# Sheet1.net
KiCad netlist of a schematic drawn in Altium Designer
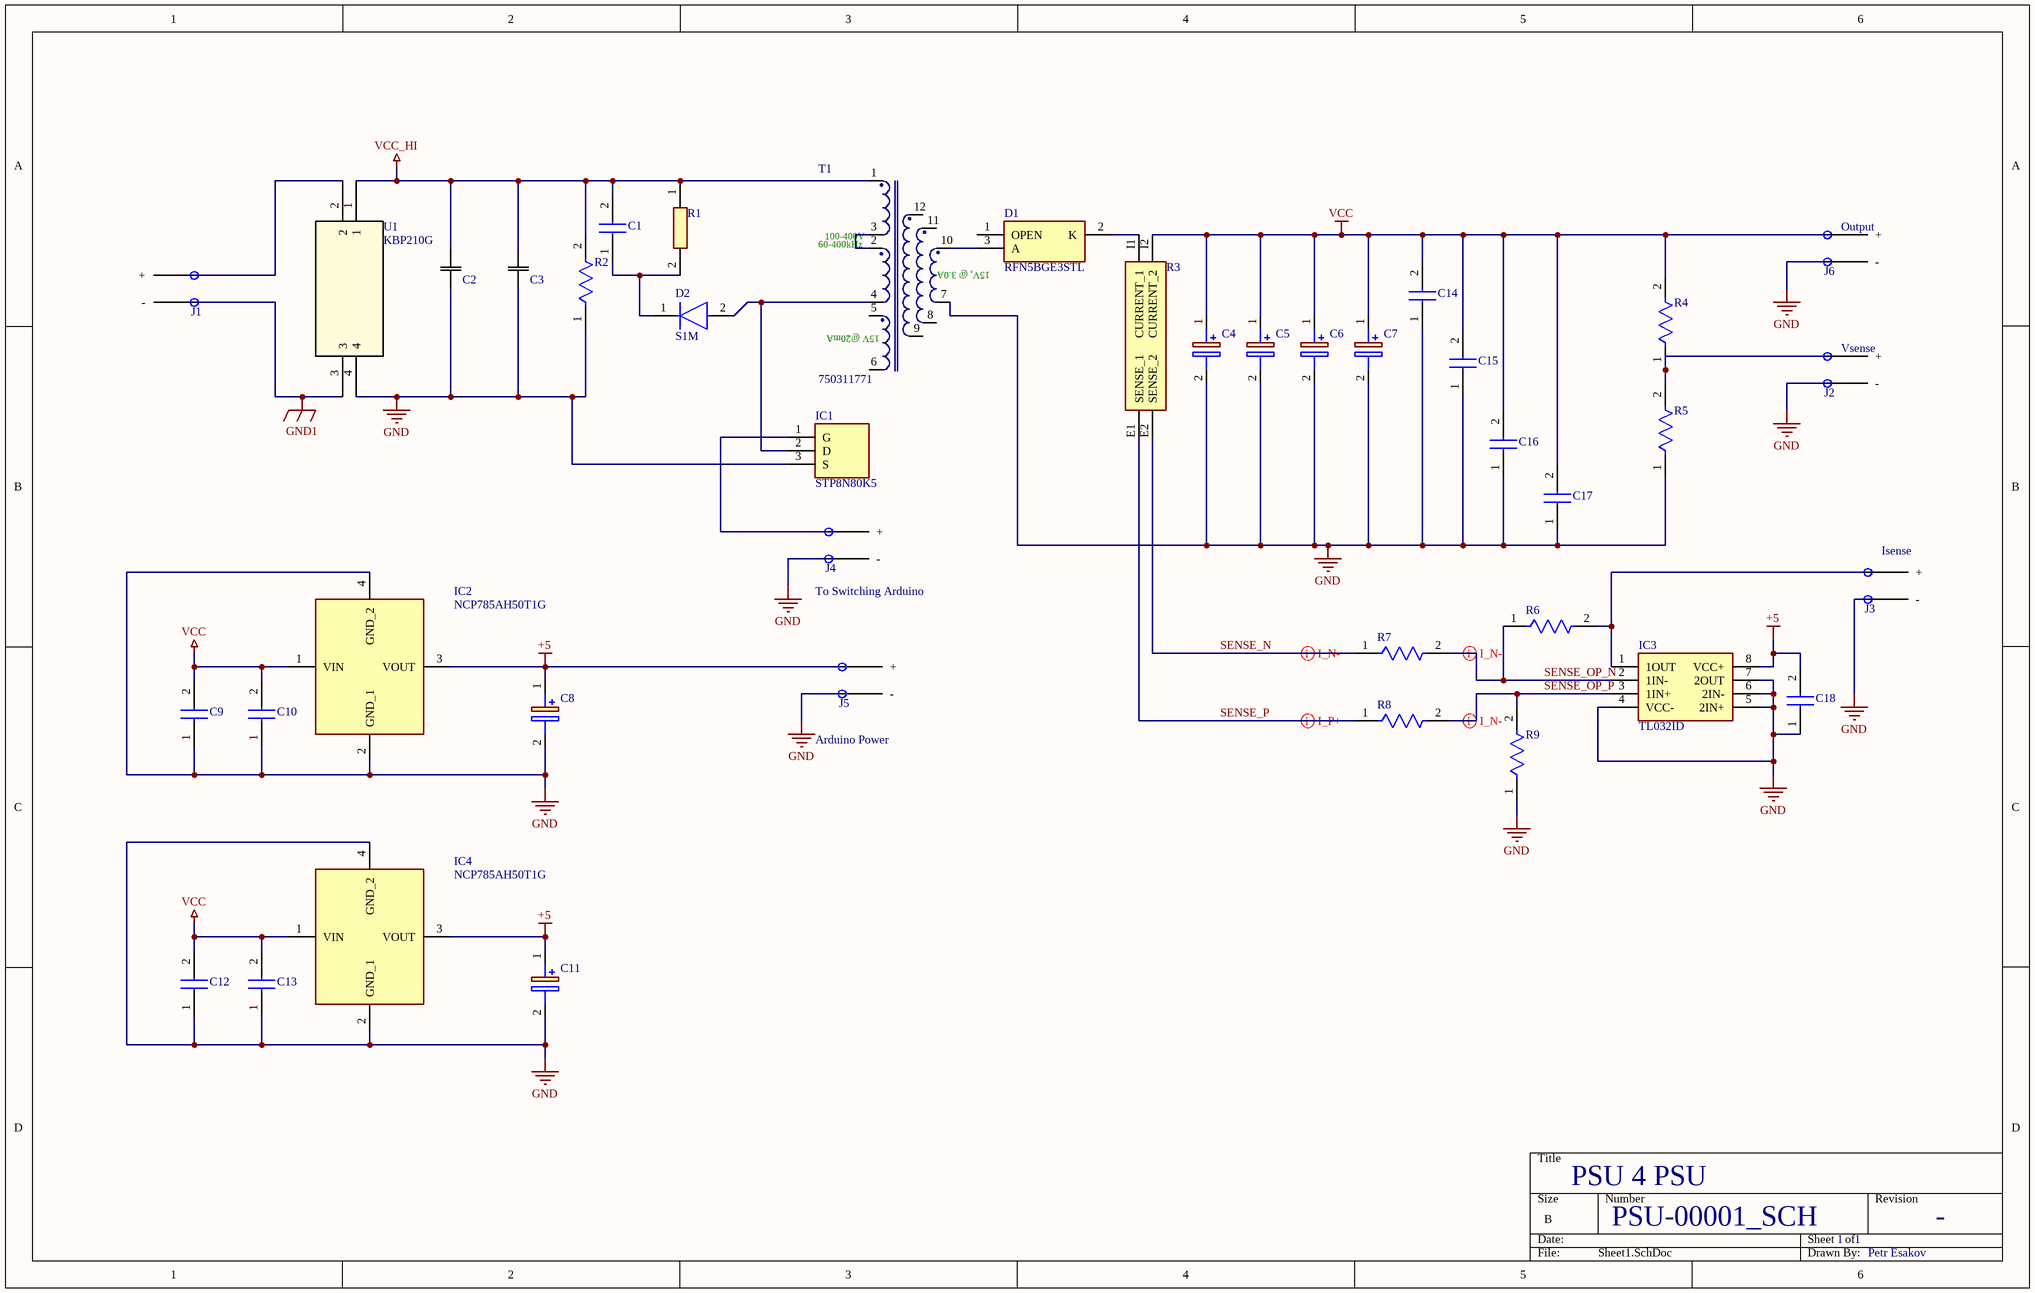
[diagram p0: Sheet1.SchDoc]

(export (version "E")
  (design (tool "Eeschema 10.0.6"))
  (components
    (comp (ref "C1")
      (value "C2220C105K2RACTU")
      (footprint "SamacSys:C2220")
      (description "Capacitor")
      (libsource (lib "*") (part "C2220C105K2RACTU"))
    )
    (comp (ref "C2")
      (value "500HXW100MEFR18X45")
      (footprint "CAP_HXW_18X45_RUB")
      (description "No Description Available")
      (libsource (lib "500HXW100MEFR18X45") (part "500HXW100MEFR18X45"))
    )
    (comp (ref "C3")
      (value "500HXW100MEFR18X45")
      (footprint "CAP_HXW_18X45_RUB")
      (description "No Description Available")
      (libsource (lib "500HXW100MEFR18X45") (part "500HXW100MEFR18X45"))
    )
    (comp (ref "C4")
      (value "EGXF630ELL511MK25S")
      (footprint "SamacSys:CAPPRD500W60D1275H2650")
      (description "Capacitor Polarised")
      (fields (field (name "MOUSER PART NUMBER") "661-EGXF630ELL511MK2"))
      (libsource (lib "*") (part "EGXF630ELL511MK25S"))
    )
    (comp (ref "C5")
      (value "EGXF630ELL511MK25S")
      (footprint "SamacSys:CAPPRD500W60D1275H2650")
      (description "Capacitor Polarised")
      (fields (field (name "MOUSER PART NUMBER") "661-EGXF630ELL511MK2"))
      (libsource (lib "*") (part "EGXF630ELL511MK25S"))
    )
    (comp (ref "C6")
      (value "EGXF630ELL511MK25S")
      (footprint "SamacSys:CAPPRD500W60D1275H2650")
      (description "Capacitor Polarised")
      (fields (field (name "MOUSER PART NUMBER") "661-EGXF630ELL511MK2"))
      (libsource (lib "*") (part "EGXF630ELL511MK25S"))
    )
    (comp (ref "C7")
      (value "EGXF630ELL511MK25S")
      (footprint "SamacSys:CAPPRD500W60D1275H2650")
      (description "Capacitor Polarised")
      (fields (field (name "MOUSER PART NUMBER") "661-EGXF630ELL511MK2"))
      (libsource (lib "*") (part "EGXF630ELL511MK25S"))
    )
    (comp (ref "C8")
      (value "MAL202139229E3")
      (footprint "SamacSys:CAPPA4610W80L1850D690")
      (description "Capacitor Polarised")
      (fields (field (name "MOUSER PART NUMBER") "594-2222-021-39229"))
      (libsource (lib "*") (part "MAL202139229E3"))
    )
    (comp (ref "C9")
      (value "ECW-FD2J105J")
      (footprint "SamacSys:ECWFD2J105J")
      (description "Capacitor")
      (fields (field (name "MOUSER PART NUMBER") "667-ECW-FD2J105J"))
      (libsource (lib "*") (part "ECW-FD2J105J"))
    )
    (comp (ref "C10")
      (value "ECW-FD2J105J")
      (footprint "SamacSys:ECWFD2J105J")
      (description "Capacitor")
      (fields (field (name "MOUSER PART NUMBER") "667-ECW-FD2J105J"))
      (libsource (lib "*") (part "ECW-FD2J105J"))
    )
    (comp (ref "C11")
      (value "MAL202139229E3")
      (footprint "SamacSys:CAPPA4610W80L1850D690")
      (description "Capacitor Polarised")
      (fields (field (name "MOUSER PART NUMBER") "594-2222-021-39229"))
      (libsource (lib "*") (part "MAL202139229E3"))
    )
    (comp (ref "C12")
      (value "ECW-FD2J105J")
      (footprint "SamacSys:ECWFD2J105J")
      (description "Capacitor")
      (fields (field (name "MOUSER PART NUMBER") "667-ECW-FD2J105J"))
      (libsource (lib "*") (part "ECW-FD2J105J"))
    )
    (comp (ref "C13")
      (value "ECW-FD2J105J")
      (footprint "SamacSys:ECWFD2J105J")
      (description "Capacitor")
      (fields (field (name "MOUSER PART NUMBER") "667-ECW-FD2J105J"))
      (libsource (lib "*") (part "ECW-FD2J105J"))
    )
    (comp (ref "C14")
      (value "K104K15X7RF5TH5")
      (footprint "SamacSys:K104K15X7RF5TH5")
      (description "Capacitor")
      (fields (field (name "MOUSER PART NUMBER") "594-K104K15X7RF5TH5"))
      (libsource (lib "*") (part "K104K15X7RF5TH5"))
    )
    (comp (ref "C15")
      (value "K104K15X7RF5TH5")
      (footprint "SamacSys:K104K15X7RF5TH5")
      (description "Capacitor")
      (fields (field (name "MOUSER PART NUMBER") "594-K104K15X7RF5TH5"))
      (libsource (lib "*") (part "K104K15X7RF5TH5"))
    )
    (comp (ref "C16")
      (value "K104K15X7RF5TH5")
      (footprint "SamacSys:K104K15X7RF5TH5")
      (description "Capacitor")
      (fields (field (name "MOUSER PART NUMBER") "594-K104K15X7RF5TH5"))
      (libsource (lib "*") (part "K104K15X7RF5TH5"))
    )
    (comp (ref "C17")
      (value "K104K15X7RF5TH5")
      (footprint "SamacSys:K104K15X7RF5TH5")
      (description "Capacitor")
      (fields (field (name "MOUSER PART NUMBER") "594-K104K15X7RF5TH5"))
      (libsource (lib "*") (part "K104K15X7RF5TH5"))
    )
    (comp (ref "C18")
      (value "K104K15X7RF5TH5")
      (footprint "SamacSys:K104K15X7RF5TH5")
      (description "Capacitor")
      (fields (field (name "MOUSER PART NUMBER") "594-K104K15X7RF5TH5"))
      (libsource (lib "*") (part "K104K15X7RF5TH5"))
    )
    (comp (ref "D1")
      (value "RFN5BGE3STL")
      (footprint "SamacSys:RD3P175SNFRATL")
      (description "Diode")
      (fields (field (name "MOUSER PART NUMBER") "755-RFN5BGE3STL"))
      (libsource (lib "*") (part "RFN5BGE3STL"))
    )
    (comp (ref "D2")
      (value "S1M")
      (footprint "FP-403AE-MFG")
      (description "DIODE GEN PURP 1KV 1A SMA")
      (fields (field (name "VOLTAGE") "1kV"))
      (libsource (lib "Altium Content Vault") (part "d7152d700b627762746794eb795d46e"))
    )
    (comp (ref "IC1")
      (value "STP8N80K5")
      (footprint "SamacSys:TO255P460X1020X2008-3P")
      (description "Integrated Circuit")
      (fields (field (name "MOUSER PART NUMBER") "511-STP8N80K5"))
      (libsource (lib "*") (part "STP8N80K5"))
    )
    (comp (ref "IC2")
      (value "NCP785AH50T1G")
      (footprint "SamacSys:NCP785AH50T1G")
      (description "Integrated Circuit")
      (fields (field (name "MOUSER PART NUMBER") "863-NCP785AH50T1G"))
      (libsource (lib "*") (part "NCP785AH50T1G"))
    )
    (comp (ref "IC3")
      (value "TL032ID")
      (footprint "SamacSys:SOIC127P600X175-8N")
      (description "Integrated Circuit")
      (fields (field (name "MOUSER PART NUMBER") "595-TL032ID"))
      (libsource (lib "*") (part "TL032ID"))
    )
    (comp (ref "IC4")
      (value "NCP785AH50T1G")
      (footprint "SamacSys:NCP785AH50T1G")
      (description "Integrated Circuit")
      (fields (field (name "MOUSER PART NUMBER") "863-NCP785AH50T1G"))
      (libsource (lib "*") (part "NCP785AH50T1G"))
    )
    (comp (ref "J1")
      (value "Component_1")
      (footprint "PCBComponent_1")
      (libsource (lib "Integrated_Library1") (part "Component_1"))
    )
    (comp (ref "J2")
      (value "Component_1")
      (footprint "PCBComponent_1")
      (libsource (lib "Integrated_Library1") (part "Component_1"))
    )
    (comp (ref "J3")
      (value "Component_1")
      (footprint "PCBComponent_1")
      (libsource (lib "Integrated_Library1") (part "Component_1"))
    )
    (comp (ref "J4")
      (value "Component_1")
      (footprint "PCBComponent_1")
      (libsource (lib "Integrated_Library1") (part "Component_1"))
    )
    (comp (ref "J5")
      (value "Component_1")
      (footprint "PCBComponent_1")
      (libsource (lib "Integrated_Library1") (part "Component_1"))
    )
    (comp (ref "J6")
      (value "Component_1")
      (footprint "PCBComponent_1")
      (libsource (lib "Integrated_Library1") (part "Component_1"))
    )
    (comp (ref "R1")
      (value "MRS25000C7500FRP00")
      (footprint "SamacSys:RESAD1650W60L650D250")
      (description "Resistor")
      (libsource (lib "*") (part "MRS25000C7500FRP00"))
    )
    (comp (ref "R2")
      (value "CRCW251210K0JNEG")
      (footprint "FP-CRCW2512-e3-IPC_A")
      (description "RES Thick Film, 10kΩ, 5%, 1W, 200ppm/°C, 2512")
      (fields (field (name "TOLERANCE") "5%"))
      (libsource (lib "Altium Content Vault") (part "1029c3af85768c4190bb7ad29bc67b5"))
    )
    (comp (ref "R3")
      (value "Y14870R10000B9R")
      (footprint "SamacSys:Y14870R10000B9R")
      (description "Resistor")
      (fields (field (name "MOUSER PART NUMBER") "71-CSM25120R1000BST"))
      (libsource (lib "*") (part "Y14870R10000B9R"))
    )
    (comp (ref "R4")
      (value "CR0805-FX-1003ELF")
      (footprint "FP-CR0805-IPC_B")
      (description "Thick Film Chip Resistors 0805 100kΩ 0.125W 1% 100ppm/°C")
      (fields (field (name "TOLERANCE") "1%"))
      (libsource (lib "Altium Content Vault") (part "1029c3af85768c4190bb7ad29bc67b5"))
    )
    (comp (ref "R5")
      (value "CRCW080520K0FKTA")
      (footprint "FP-CRCW0805-e3-IPC_B")
      (description "RES Thick Film, 20kΩ, 1%, 0.125W, 100ppm/°C, 0805")
      (fields (field (name "TOLERANCE") "1%"))
      (libsource (lib "Altium Content Vault") (part "1029c3af85768c4190bb7ad29bc67b5"))
    )
    (comp (ref "R6")
      (value "CRCW0805330KFKEA")
      (footprint "FP-CRCW0805-e3-MFG")
      (description "RES Thick Film, 330kΩ, 1%, 0.125W, 100ppm/°C, 0805")
      (fields (field (name "TOLERANCE") "1%"))
      (libsource (lib "Altium Content Vault") (part "1029c3af85768c4190bb7ad29bc67b5"))
    )
    (comp (ref "R7")
      (value "CRCW080520K0FKEB")
      (footprint "FP-CRCW0805-e3-IPC_B")
      (description "RES Thick Film, 20kΩ, 1%, 0.125W, 100ppm/°C, 0805")
      (fields (field (name "TOLERANCE") "1%"))
      (libsource (lib "Altium Content Vault") (part "1029c3af85768c4190bb7ad29bc67b5"))
    )
    (comp (ref "R8")
      (value "CRCW080520K0FKEB")
      (footprint "FP-CRCW0805-e3-IPC_B")
      (description "RES Thick Film, 20kΩ, 1%, 0.125W, 100ppm/°C, 0805")
      (fields (field (name "TOLERANCE") "1%"))
      (libsource (lib "Altium Content Vault") (part "1029c3af85768c4190bb7ad29bc67b5"))
    )
    (comp (ref "R9")
      (value "CRCW0805330KFKEA")
      (footprint "FP-CRCW0805-e3-MFG")
      (description "RES Thick Film, 330kΩ, 1%, 0.125W, 100ppm/°C, 0805")
      (fields (field (name "TOLERANCE") "1%"))
      (libsource (lib "Altium Content Vault") (part "1029c3af85768c4190bb7ad29bc67b5"))
    )
    (comp (ref "T1")
      (value "750311771")
      (footprint "EFD25")
      (description "Flyback Transformer suitable or LT3573/ LT3574/ LT3575/ LT3748 WE-FB, Ui=100-400V")
      (fields (field (name "MANUFACTURER") "Wuerth Elektronik"))
      (libsource (lib "Altium Content Vault") (part "WE-750311771"))
    )
    (comp (ref "U1")
      (value "KBP210G")
      (footprint "TO_P2005G_DIO")
      (description "No Description Available")
      (libsource (lib "KBP210G") (part "KBP210G"))
    )
  )
  (nets
    (net (code "1") (name "+5") (class "Default")
      (node (ref "C11") (pin "1") (pinfunction "+_1") (pintype "passive"))
      (node (ref "C18") (pin "2") (pinfunction "2_2") (pintype "passive"))
      (node (ref "C8") (pin "1") (pinfunction "+_1") (pintype "passive"))
      (node (ref "IC2") (pin "3") (pinfunction "VOUT_3") (pintype "passive"))
      (node (ref "IC3") (pin "8") (pinfunction "VCC+_8") (pintype "passive"))
      (node (ref "IC4") (pin "3") (pinfunction "VOUT_3") (pintype "passive"))
      (node (ref "J5") (pin "0") (pinfunction "+_0") (pintype "passive"))
    )
    (net (code "2") (name "/SENSE_N") (class "Default")
      (node (ref "R3") (pin "E2") (pinfunction "SENSE_2_E2") (pintype "passive"))
      (node (ref "R7") (pin "1") (pinfunction "1_1") (pintype "passive"))
    )
    (net (code "3") (name "/SENSE_OP_N") (class "Default")
      (node (ref "IC3") (pin "2") (pinfunction "1IN-_2") (pintype "passive"))
      (node (ref "R6") (pin "1") (pinfunction "1_1") (pintype "passive"))
      (node (ref "R7") (pin "2") (pinfunction "2_2") (pintype "passive"))
    )
    (net (code "4") (name "/SENSE_OP_P") (class "Default")
      (node (ref "IC3") (pin "3") (pinfunction "1IN+_3") (pintype "passive"))
      (node (ref "R8") (pin "2") (pinfunction "2_2") (pintype "passive"))
      (node (ref "R9") (pin "2") (pinfunction "2_2") (pintype "passive"))
    )
    (net (code "5") (name "/SENSE_P") (class "Default")
      (node (ref "R3") (pin "E1") (pinfunction "SENSE_1_E1") (pintype "passive"))
      (node (ref "R8") (pin "1") (pinfunction "1_1") (pintype "passive"))
    )
    (net (code "6") (name "GND") (class "Default")
      (node (ref "C10") (pin "1") (pinfunction "1_1") (pintype "passive"))
      (node (ref "C11") (pin "2") (pinfunction "-_2") (pintype "passive"))
      (node (ref "C12") (pin "1") (pinfunction "1_1") (pintype "passive"))
      (node (ref "C13") (pin "1") (pinfunction "1_1") (pintype "passive"))
      (node (ref "C14") (pin "1") (pinfunction "1_1") (pintype "passive"))
      (node (ref "C15") (pin "1") (pinfunction "1_1") (pintype "passive"))
      (node (ref "C16") (pin "1") (pinfunction "1_1") (pintype "passive"))
      (node (ref "C17") (pin "1") (pinfunction "1_1") (pintype "passive"))
      (node (ref "C18") (pin "1") (pinfunction "1_1") (pintype "passive"))
      (node (ref "C2") (pin "1") (pinfunction "1_1") (pintype "passive"))
      (node (ref "C3") (pin "1") (pinfunction "1_1") (pintype "passive"))
      (node (ref "C4") (pin "2") (pinfunction "-_2") (pintype "passive"))
      (node (ref "C5") (pin "2") (pinfunction "-_2") (pintype "passive"))
      (node (ref "C6") (pin "2") (pinfunction "-_2") (pintype "passive"))
      (node (ref "C7") (pin "2") (pinfunction "-_2") (pintype "passive"))
      (node (ref "C8") (pin "2") (pinfunction "-_2") (pintype "passive"))
      (node (ref "C9") (pin "1") (pinfunction "1_1") (pintype "passive"))
      (node (ref "IC1") (pin "3") (pinfunction "S_3") (pintype "passive"))
      (node (ref "IC2") (pin "2") (pinfunction "GND_1_2") (pintype "passive"))
      (node (ref "IC2") (pin "4") (pinfunction "GND_2_4") (pintype "passive"))
      (node (ref "IC3") (pin "4") (pinfunction "VCC-_4") (pintype "passive"))
      (node (ref "IC3") (pin "5") (pinfunction "2IN+_5") (pintype "passive"))
      (node (ref "IC3") (pin "6") (pinfunction "2IN-_6") (pintype "passive"))
      (node (ref "IC3") (pin "7") (pinfunction "2OUT_7") (pintype "passive"))
      (node (ref "IC4") (pin "2") (pinfunction "GND_1_2") (pintype "passive"))
      (node (ref "IC4") (pin "4") (pinfunction "GND_2_4") (pintype "passive"))
      (node (ref "J2") (pin "1") (pinfunction "-_1") (pintype "passive"))
      (node (ref "J3") (pin "1") (pinfunction "-_1") (pintype "passive"))
      (node (ref "J4") (pin "1") (pinfunction "-_1") (pintype "passive"))
      (node (ref "J5") (pin "1") (pinfunction "-_1") (pintype "passive"))
      (node (ref "J6") (pin "1") (pinfunction "-_1") (pintype "passive"))
      (node (ref "R2") (pin "1") (pinfunction "1_1") (pintype "passive"))
      (node (ref "R5") (pin "1") (pinfunction "1_1") (pintype "passive"))
      (node (ref "R9") (pin "1") (pinfunction "1_1") (pintype "passive"))
      (node (ref "T1") (pin "7") (pinfunction "7_7") (pintype "passive"))
      (node (ref "U1") (pin "4") (pinfunction "4_4") (pintype "passive"))
    )
    (net (code "7") (name "GND1") (class "Default")
      (node (ref "J1") (pin "1") (pinfunction "-_1") (pintype "passive"))
      (node (ref "U1") (pin "3") (pinfunction "3_3") (pintype "passive"))
    )
    (net (code "8") (name "Net-(D1-A)") (class "Default")
      (node (ref "D1") (pin "3") (pinfunction "A_3") (pintype "passive"))
      (node (ref "T1") (pin "10") (pinfunction "10_10") (pintype "passive"))
    )
    (net (code "9") (name "Net-(D1-K)") (class "Default")
      (node (ref "D1") (pin "2") (pinfunction "K_2") (pintype "passive"))
      (node (ref "R3") (pin "I1") (pinfunction "CURRENT_1_I1") (pintype "passive"))
    )
    (net (code "10") (name "Net-(D2-A)") (class "Default")
      (node (ref "D2") (pin "2") (pinfunction "A_2") (pintype "passive"))
      (node (ref "IC1") (pin "2") (pinfunction "D_2") (pintype "passive"))
      (node (ref "T1") (pin "4") (pinfunction "4_4") (pintype "passive"))
    )
    (net (code "11") (name "Net-(D2-C)") (class "Default")
      (node (ref "C1") (pin "1") (pinfunction "1_1") (pintype "passive"))
      (node (ref "D2") (pin "1") (pinfunction "C_1") (pintype "passive"))
      (node (ref "R1") (pin "2") (pinfunction "2_2") (pintype "passive"))
    )
    (net (code "12") (name "Net-(IC1-G)") (class "Default")
      (node (ref "IC1") (pin "1") (pinfunction "G_1") (pintype "passive"))
      (node (ref "J4") (pin "0") (pinfunction "+_0") (pintype "passive"))
    )
    (net (code "13") (name "Net-(IC3-1OUT)") (class "Default")
      (node (ref "IC3") (pin "1") (pinfunction "1OUT_1") (pintype "passive"))
      (node (ref "J3") (pin "0") (pinfunction "+_0") (pintype "passive"))
      (node (ref "R6") (pin "2") (pinfunction "2_2") (pintype "passive"))
    )
    (net (code "14") (name "Net-(J1-+)") (class "Default")
      (node (ref "J1") (pin "0") (pinfunction "+_0") (pintype "passive"))
      (node (ref "U1") (pin "2") (pinfunction "2_2") (pintype "passive"))
    )
    (net (code "15") (name "Net-(J2-+)") (class "Default")
      (node (ref "J2") (pin "0") (pinfunction "+_0") (pintype "passive"))
      (node (ref "R4") (pin "1") (pinfunction "1_1") (pintype "passive"))
      (node (ref "R5") (pin "2") (pinfunction "2_2") (pintype "passive"))
    )
    (net (code "16") (name "Net-(T1-Pad2)") (class "Default")
      (node (ref "T1") (pin "2") (pinfunction "2_2") (pintype "passive"))
      (node (ref "T1") (pin "3") (pinfunction "3_3") (pintype "passive"))
    )
    (net (code "17") (name "VCC") (class "Default")
      (node (ref "C10") (pin "2") (pinfunction "2_2") (pintype "passive"))
      (node (ref "C12") (pin "2") (pinfunction "2_2") (pintype "passive"))
      (node (ref "C13") (pin "2") (pinfunction "2_2") (pintype "passive"))
      (node (ref "C14") (pin "2") (pinfunction "2_2") (pintype "passive"))
      (node (ref "C15") (pin "2") (pinfunction "2_2") (pintype "passive"))
      (node (ref "C16") (pin "2") (pinfunction "2_2") (pintype "passive"))
      (node (ref "C17") (pin "2") (pinfunction "2_2") (pintype "passive"))
      (node (ref "C4") (pin "1") (pinfunction "+_1") (pintype "passive"))
      (node (ref "C5") (pin "1") (pinfunction "+_1") (pintype "passive"))
      (node (ref "C6") (pin "1") (pinfunction "+_1") (pintype "passive"))
      (node (ref "C7") (pin "1") (pinfunction "+_1") (pintype "passive"))
      (node (ref "C9") (pin "2") (pinfunction "2_2") (pintype "passive"))
      (node (ref "IC2") (pin "1") (pinfunction "VIN_1") (pintype "passive"))
      (node (ref "IC4") (pin "1") (pinfunction "VIN_1") (pintype "passive"))
      (node (ref "J6") (pin "0") (pinfunction "+_0") (pintype "passive"))
      (node (ref "R3") (pin "I2") (pinfunction "CURRENT_2_I2") (pintype "passive"))
      (node (ref "R4") (pin "2") (pinfunction "2_2") (pintype "passive"))
    )
    (net (code "18") (name "VCC_HI") (class "Default")
      (node (ref "C1") (pin "2") (pinfunction "2_2") (pintype "passive"))
      (node (ref "C2") (pin "2") (pinfunction "2_2") (pintype "passive"))
      (node (ref "C3") (pin "2") (pinfunction "2_2") (pintype "passive"))
      (node (ref "R1") (pin "1") (pinfunction "1_1") (pintype "passive"))
      (node (ref "R2") (pin "2") (pinfunction "2_2") (pintype "passive"))
      (node (ref "T1") (pin "1") (pinfunction "1_1") (pintype "passive"))
      (node (ref "U1") (pin "1") (pinfunction "1_1") (pintype "passive"))
    )
    (net (code "19") (name "unconnected-(D1-OPEN-Pad1)") (class "Default")
      (node (ref "D1") (pin "1") (pinfunction "OPEN_1") (pintype "passive"))
    )
    (net (code "20") (name "unconnected-(T1-Pad5)") (class "Default")
      (node (ref "T1") (pin "5") (pinfunction "5_5") (pintype "passive"))
    )
    (net (code "21") (name "unconnected-(T1-Pad6)") (class "Default")
      (node (ref "T1") (pin "6") (pinfunction "6_6") (pintype "passive"))
    )
    (net (code "22") (name "unconnected-(T1-Pad8)") (class "Default")
      (node (ref "T1") (pin "8") (pinfunction "8_8") (pintype "passive"))
    )
    (net (code "23") (name "unconnected-(T1-Pad9)") (class "Default")
      (node (ref "T1") (pin "9") (pinfunction "9_9") (pintype "passive"))
    )
    (net (code "24") (name "unconnected-(T1-Pad11)") (class "Default")
      (node (ref "T1") (pin "11") (pinfunction "11_11") (pintype "passive"))
    )
    (net (code "25") (name "unconnected-(T1-Pad12)") (class "Default")
      (node (ref "T1") (pin "12") (pinfunction "12_12") (pintype "passive"))
    )
  )
)
